# 002_PowerSupply.net
KiCad netlist of a schematic drawn in Altium Designer
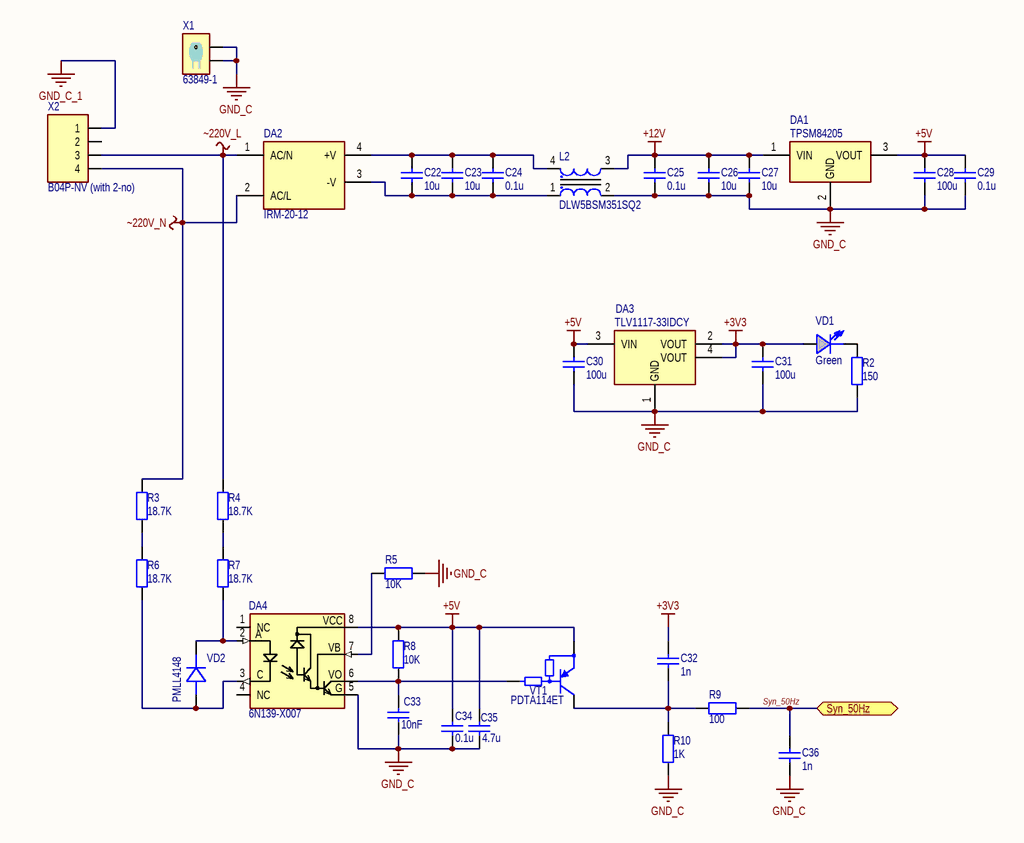
[diagram p0: 002_PowerSupply.SchDoc]

(export (version "E")
  (design (tool "Eeschema 10.0.6"))
  (components
    (comp (ref "C22")
      (value "10u")
      (footprint "mainLib:SMD_C_1206")
      (description "SMD C 1206 MURATA 25V 20% X5R")
      (fields (field (name "PARTNUMBER") "GRM31MR61E106M") (field (name "MANUFACTURER") "MURATA"))
      (libsource (lib "mainRCLib") (part "C1206 10u 25V 20%"))
    )
    (comp (ref "C23")
      (value "10u")
      (footprint "mainLib:SMD_C_1206")
      (description "SMD C 1206 MURATA 25V 20% X5R")
      (fields (field (name "PARTNUMBER") "GRM31MR61E106M") (field (name "MANUFACTURER") "MURATA"))
      (libsource (lib "mainRCLib") (part "C1206 10u 25V 20%"))
    )
    (comp (ref "C24")
      (value "0.1u")
      (footprint "mainLib:SMD_C_0603")
      (description "SMD C 0603 MURATA 50V 10% X7R")
      (fields (field (name "PARTNUMBER") "GRM188R71H104K") (field (name "MANUFACTURER") "MURATA"))
      (libsource (lib "mainRCLib") (part "C0603 0.1u 50V 10%"))
    )
    (comp (ref "C25")
      (value "0.1u")
      (footprint "mainLib:SMD_C_0603")
      (description "SMD C 0603 MURATA 50V 10% X7R")
      (fields (field (name "PARTNUMBER") "GRM188R71H104K") (field (name "MANUFACTURER") "MURATA"))
      (libsource (lib "mainRCLib") (part "C0603 0.1u 50V 10%"))
    )
    (comp (ref "C26")
      (value "10u")
      (footprint "mainLib:SMD_C_1206")
      (description "SMD C 1206 MURATA 25V 20% X5R")
      (fields (field (name "PARTNUMBER") "GRM31MR61E106M") (field (name "MANUFACTURER") "MURATA"))
      (libsource (lib "mainRCLib") (part "C1206 10u 25V 20%"))
    )
    (comp (ref "C27")
      (value "10u")
      (footprint "mainLib:SMD_C_1206")
      (description "SMD C 1206 MURATA 25V 20% X5R")
      (fields (field (name "PARTNUMBER") "GRM31MR61E106M") (field (name "MANUFACTURER") "MURATA"))
      (libsource (lib "mainRCLib") (part "C1206 10u 25V 20%"))
    )
    (comp (ref "C28")
      (value "100u")
      (footprint "mainLib:SMD_C_0805")
      (description "SMD 0805 MURATA 6.3V 20% X5R")
      (fields (field (name "PARTNUMBER") "GRM21BR60J107M") (field (name "MANUFACTURER") "MURATA"))
      (libsource (lib "mainRCLib") (part "C0805 100u 6.3V 20% X5R"))
    )
    (comp (ref "C29")
      (value "0.1u")
      (footprint "mainLib:SMD_C_0603")
      (description "SMD C 0603 MURATA 50V 10% X7R")
      (fields (field (name "PARTNUMBER") "GRM188R71H104K") (field (name "MANUFACTURER") "MURATA"))
      (libsource (lib "mainRCLib") (part "C0603 0.1u 50V 10%"))
    )
    (comp (ref "C30")
      (value "100u")
      (footprint "mainLib:SMD_C_0805")
      (description "SMD 0805 MURATA 6.3V 20% X5R")
      (fields (field (name "PARTNUMBER") "GRM21BR60J107M") (field (name "MANUFACTURER") "MURATA"))
      (libsource (lib "mainRCLib") (part "C0805 100u 6.3V 20% X5R"))
    )
    (comp (ref "C31")
      (value "100u")
      (footprint "mainLib:SMD_C_0805")
      (description "SMD 0805 MURATA 6.3V 20% X5R")
      (fields (field (name "PARTNUMBER") "GRM21BR60J107M") (field (name "MANUFACTURER") "MURATA"))
      (libsource (lib "mainRCLib") (part "C0805 100u 6.3V 20% X5R"))
    )
    (comp (ref "C32")
      (value "1n")
      (footprint "mainLib:SMD_C_0603")
      (description "SMD C 0603 MURATA 50V 5% NP0")
      (fields (field (name "PARTNUMBER") "GRM1885C1H102JA01") (field (name "MANUFACTURER") "MURATA"))
      (libsource (lib "mainRCLib") (part "C0603 1n 50V 5%"))
    )
    (comp (ref "C33")
      (value "10nF")
      (footprint "mainLib:SMD_C_0603")
      (description "SMD C 0603 MURATA 100V 10% X7R")
      (fields (field (name "PARTNUMBER") "GRJ188R72A103KE11#") (field (name "MANUFACTURER") "MURATA"))
      (libsource (lib "mainRCLib") (part "C0603 10nF 100V 10%"))
    )
    (comp (ref "C34")
      (value "0.1u")
      (footprint "mainLib:SMD_C_0603")
      (description "SMD C 0603 MURATA 50V 10% X7R")
      (fields (field (name "PARTNUMBER") "GRM188R71H104K") (field (name "MANUFACTURER") "MURATA"))
      (libsource (lib "mainRCLib") (part "C0603 0.1u 50V 10%"))
    )
    (comp (ref "C35")
      (value "4.7u")
      (footprint "mainLib:SMD_C_0805")
      (description "SMD C 0805 MURATA 50V 5% NP0")
      (fields (field (name "PARTNUMBER") "GRM21BR61E475M") (field (name "MANUFACTURER") "MURATA"))
      (libsource (lib "mainRCLib") (part "C0805 4.7u 25V 20%  X5R"))
    )
    (comp (ref "C36")
      (value "1n")
      (footprint "mainLib:SMD_C_0603")
      (description "SMD C 0603 MURATA 50V 5% NP0")
      (fields (field (name "PARTNUMBER") "GRM1885C1H102JA01") (field (name "MANUFACTURER") "MURATA"))
      (libsource (lib "mainRCLib") (part "C0603 1n 50V 5%"))
    )
    (comp (ref "DA1")
      (value "TPSM84205")
      (footprint "mainLib:EAB (SIP DCDC Module)")
      (description "1.5A 5Vout up to 28 Vin StepDown module")
      (fields (field (name "MANUFACTURER") "Texas Instrument"))
      (libsource (lib "mainLib") (part "TPSM84205"))
    )
    (comp (ref "DA2")
      (value "IRM-20-12")
      (footprint "mainLib:IRM-20-12")
      (description "20W 12VDC 1.85A PCB")
      (fields (field (name "MANUFACTURER") "Mean Well"))
      (libsource (lib "mainLib") (part "IRM-20-12"))
    )
    (comp (ref "DA3")
      (value "TLV1117-33IDCY")
      (footprint "mainLib:SOT-223_M")
      (description "Voltage regulator 3.3V 800mA")
      (fields (field (name "MANUFACTURER") "Texas Instrument"))
      (libsource (lib "mainLib") (part "TLV1117-33IDCY"))
    )
    (comp (ref "DA4")
      (value "6N139-X007")
      (footprint "mainLib:6N139-X007")
      (description "Optocoupler darlingron 5.3kV 100 kbit/s")
      (fields (field (name "MANUFACTURER") "Vishay"))
      (libsource (lib "mainLib") (part "6N139-X007"))
    )
    (comp (ref "L2")
      (value "DLW5BSM351SQ2")
      (footprint "mainLib:DLW5BS(AH)")
      (description "SMD Common Mode Choke Coil 2A Z = 350 Ohm / 100 MHz")
      (fields (field (name "MANUFACTURER") "MURATA"))
      (libsource (lib "mainLib") (part "DLW5BSM351SQ2"))
    )
    (comp (ref "R2")
      (value "150")
      (footprint "mainLib:SMD_R_0805")
      (description "SMD 0805 VISHAY 0.125W 150V 1% 100ppm")
      (fields (field (name "PARTNUMBER") "CRCW0805150RFK") (field (name "MANUFACTURER") "VISHAY"))
      (libsource (lib "mainRCLib") (part "R0805 150 1%"))
    )
    (comp (ref "R3")
      (value "18.7K")
      (footprint "mainLib:SMD_R_1206")
      (description "SMD R 1206 VISHAY 0.25W 200V 1% 100ppm")
      (fields (field (name "PARTNUMBER") "CRCW120618K7FK") (field (name "MANUFACTURER") "VISHAY"))
      (libsource (lib "mainRCLib") (part "R1206 18.7K 1%"))
    )
    (comp (ref "R4")
      (value "18.7K")
      (footprint "mainLib:SMD_R_1206")
      (description "SMD R 1206 VISHAY 0.25W 200V 1% 100ppm")
      (fields (field (name "PARTNUMBER") "CRCW120618K7FK") (field (name "MANUFACTURER") "VISHAY"))
      (libsource (lib "mainRCLib") (part "R1206 18.7K 1%"))
    )
    (comp (ref "R5")
      (value "10K")
      (footprint "SMD_R_0603")
      (description "SMD R 0603 VISHAY 0.1W 75V 1% 100ppm")
      (fields (field (name "PARTNUMBER") "CRCW060310K0FK") (field (name "MANUFACTURER") "VISHAY"))
      (libsource (lib "mainRCLib") (part "R0603 10К 1%"))
    )
    (comp (ref "R6")
      (value "18.7K")
      (footprint "mainLib:SMD_R_1206")
      (description "SMD R 1206 VISHAY 0.25W 200V 1% 100ppm")
      (fields (field (name "PARTNUMBER") "CRCW120618K7FK") (field (name "MANUFACTURER") "VISHAY"))
      (libsource (lib "mainRCLib") (part "R1206 18.7K 1%"))
    )
    (comp (ref "R7")
      (value "18.7K")
      (footprint "mainLib:SMD_R_1206")
      (description "SMD R 1206 VISHAY 0.25W 200V 1% 100ppm")
      (fields (field (name "PARTNUMBER") "CRCW120618K7FK") (field (name "MANUFACTURER") "VISHAY"))
      (libsource (lib "mainRCLib") (part "R1206 18.7K 1%"))
    )
    (comp (ref "R8")
      (value "10K")
      (footprint "mainLib:SMD_R_0805")
      (description "SMD R 0805 VISHAY 0.125W 150V 1% 100ppm")
      (fields (field (name "PARTNUMBER") "CRCW080510K0FK") (field (name "MANUFACTURER") "VISHAY"))
      (libsource (lib "mainRCLib") (part "R0805 10K 1%"))
    )
    (comp (ref "R9")
      (value "100")
      (footprint "SMD_R_0603")
      (description "SMD R 0603 VISHAY 0.1W 75V 1% 100ppm")
      (fields (field (name "PARTNUMBER") "CRCW0603100RFK") (field (name "MANUFACTURER") "VISHAY"))
      (libsource (lib "mainRCLib") (part "R0603 100 1%"))
    )
    (comp (ref "R10")
      (value "1K")
      (footprint "mainLib:SMD_R_0603")
      (description "SMD R 0603 VISHAY 0.1W 75V 1% 100ppm")
      (fields (field (name "PARTNUMBER") "CRCW06031K00FK") (field (name "MANUFACTURER") "VISHAY"))
      (libsource (lib "mainRCLib") (part "R0603 1K 1%"))
    )
    (comp (ref "VD1")
      (value "Green")
      (footprint "mainLib:SMD_LED_LL_Green")
      (description "LED Green SMD")
      (fields (field (name "PARTNUMBER") "LL-S172GC-2A") (field (name "MANUFACTURER") "Lucky Light"))
      (libsource (lib "mainLib") (part "LL-S172GC-2A"))
    )
    (comp (ref "VD2")
      (value "PMLL4148")
      (footprint "mainLib:SOD80C")
      (description "If=0.2A, Vf=1V Vrrm=100V Diode (SOD80C)")
      (fields (field (name "MANUFACTURER") "NXP Semiconductors"))
      (libsource (lib "mainLib") (part "PMLL4148"))
    )
    (comp (ref "VT1")
      (value "PDTA114ET")
      (footprint "mainLib:SOT23-3")
      (description "Digital Transistor (BRT), R1=10 kOhm, R2=10 kOhm, PNP Transistor")
      (fields (field (name "MANUFACTURER") "NXP"))
      (libsource (lib "mainLib") (part "PDTA114ET"))
    )
    (comp (ref "X1")
      (value "63849-1")
      (footprint "mainLib:63849-1")
      (description "PCB, 6.3х0.8, hole")
      (fields (field (name "MANUFACTURER") "TE Connectivity"))
      (libsource (lib "mainLib") (part "63849-1"))
    )
    (comp (ref "X2")
      (value "B04P-NV (with 2-no)")
      (footprint "mainLib:B04P-NV (with 2-no)")
      (description "NV 4 конт LS=5.0 10A 250V PCB")
      (fields (field (name "PARTNUMBER") "B04P-NV") (field (name "MANUFACTURER") "JST"))
      (libsource (lib "mainLib") (part "B04P-NV (with 2-no)"))
    )
  )
  (nets
    (net (code "1") (name "+3V3") (class "Default")
      (node (ref "C31") (pin "1") (pinfunction "1_1") (pintype "passive"))
      (node (ref "C32") (pin "2") (pinfunction "2_2") (pintype "passive"))
      (node (ref "DA3") (pin "2") (pinfunction "VOUT_2") (pintype "power_in"))
      (node (ref "DA3") (pin "4") (pinfunction "VOUT_4") (pintype "power_in"))
      (node (ref "VD1") (pin "1") (pinfunction "ANODE_1") (pintype "passive"))
    )
    (net (code "2") (name "+5V") (class "Default")
      (node (ref "C28") (pin "1") (pinfunction "1_1") (pintype "passive"))
      (node (ref "C29") (pin "2") (pinfunction "2_2") (pintype "passive"))
      (node (ref "C30") (pin "1") (pinfunction "1_1") (pintype "passive"))
      (node (ref "C34") (pin "2") (pinfunction "2_2") (pintype "passive"))
      (node (ref "C35") (pin "2") (pinfunction "2_2") (pintype "passive"))
      (node (ref "DA1") (pin "3") (pinfunction "VOUT_3") (pintype "power_in"))
      (node (ref "DA3") (pin "3") (pinfunction "VIN_3") (pintype "power_in"))
      (node (ref "DA4") (pin "8") (pinfunction "VCC_8") (pintype "power_in"))
      (node (ref "R8") (pin "2") (pinfunction "2_2") (pintype "passive"))
      (node (ref "VT1") (pin "2") (pinfunction "E_2") (pintype "passive"))
    )
    (net (code "3") (name "+12V") (class "Default")
      (node (ref "C25") (pin "2") (pinfunction "2_2") (pintype "passive"))
      (node (ref "C26") (pin "2") (pinfunction "2_2") (pintype "passive"))
      (node (ref "C27") (pin "2") (pinfunction "2_2") (pintype "passive"))
      (node (ref "DA1") (pin "1") (pinfunction "VIN_1") (pintype "power_in"))
      (node (ref "L2") (pin "3") (pinfunction "3_3") (pintype "passive"))
    )
    (net (code "4") (name "/Syn_50Hz") (class "Default")
      (node (ref "C36") (pin "2") (pinfunction "2_2") (pintype "passive"))
      (node (ref "R9") (pin "2") (pinfunction "2_2") (pintype "passive"))
    )
    (net (code "5") (name "GND_C") (class "Default")
      (node (ref "C25") (pin "1") (pinfunction "1_1") (pintype "passive"))
      (node (ref "C26") (pin "1") (pinfunction "1_1") (pintype "passive"))
      (node (ref "C27") (pin "1") (pinfunction "1_1") (pintype "passive"))
      (node (ref "C28") (pin "2") (pinfunction "2_2") (pintype "passive"))
      (node (ref "C29") (pin "1") (pinfunction "1_1") (pintype "passive"))
      (node (ref "C30") (pin "2") (pinfunction "2_2") (pintype "passive"))
      (node (ref "C31") (pin "2") (pinfunction "2_2") (pintype "passive"))
      (node (ref "C33") (pin "1") (pinfunction "1_1") (pintype "passive"))
      (node (ref "C34") (pin "1") (pinfunction "1_1") (pintype "passive"))
      (node (ref "C35") (pin "1") (pinfunction "1_1") (pintype "passive"))
      (node (ref "C36") (pin "1") (pinfunction "1_1") (pintype "passive"))
      (node (ref "DA1") (pin "2") (pinfunction "GND_2") (pintype "power_in"))
      (node (ref "DA3") (pin "1") (pinfunction "GND_1") (pintype "power_in"))
      (node (ref "DA4") (pin "5") (pinfunction "5_5") (pintype "power_in"))
      (node (ref "L2") (pin "2") (pinfunction "2_2") (pintype "passive"))
      (node (ref "R10") (pin "1") (pinfunction "1_1") (pintype "passive"))
      (node (ref "R2") (pin "1") (pinfunction "1_1") (pintype "passive"))
      (node (ref "R5") (pin "2") (pinfunction "2_2") (pintype "passive"))
      (node (ref "X1") (pin "1") (pinfunction "1_1") (pintype "passive"))
      (node (ref "X1") (pin "2") (pinfunction "2_2") (pintype "passive"))
    )
    (net (code "6") (name "GND_C_1") (class "Default")
      (node (ref "X2") (pin "1") (pinfunction "1_1") (pintype "passive"))
    )
    (net (code "7") (name "Net-(DA2-+V)") (class "Default")
      (node (ref "C22") (pin "2") (pinfunction "2_2") (pintype "passive"))
      (node (ref "C23") (pin "2") (pinfunction "2_2") (pintype "passive"))
      (node (ref "C24") (pin "2") (pinfunction "2_2") (pintype "passive"))
      (node (ref "DA2") (pin "4") (pinfunction "+V_4") (pintype "passive"))
      (node (ref "L2") (pin "4") (pinfunction "4_4") (pintype "passive"))
    )
    (net (code "8") (name "Net-(DA2--V)") (class "Default")
      (node (ref "C22") (pin "1") (pinfunction "1_1") (pintype "passive"))
      (node (ref "C23") (pin "1") (pinfunction "1_1") (pintype "passive"))
      (node (ref "C24") (pin "1") (pinfunction "1_1") (pintype "passive"))
      (node (ref "DA2") (pin "3") (pinfunction "-V_3") (pintype "passive"))
      (node (ref "L2") (pin "1") (pinfunction "1_1") (pintype "passive"))
    )
    (net (code "9") (name "Net-(DA4-C)") (class "Default")
      (node (ref "DA4") (pin "3") (pinfunction "C_3") (pintype "output"))
      (node (ref "R6") (pin "1") (pinfunction "1_1") (pintype "passive"))
      (node (ref "VD2") (pin "1") (pinfunction "ANODE_1") (pintype "passive"))
    )
    (net (code "10") (name "Net-(DA4-VB)") (class "Default")
      (node (ref "DA4") (pin "7") (pinfunction "VB_7") (pintype "input"))
      (node (ref "R5") (pin "1") (pinfunction "1_1") (pintype "passive"))
    )
    (net (code "11") (name "Net-(R3-Pad1)") (class "Default")
      (node (ref "R3") (pin "1") (pinfunction "1_1") (pintype "passive"))
      (node (ref "R6") (pin "2") (pinfunction "2_2") (pintype "passive"))
    )
    (net (code "12") (name "Net-(R4-Pad1)") (class "Default")
      (node (ref "R4") (pin "1") (pinfunction "1_1") (pintype "passive"))
      (node (ref "R7") (pin "2") (pinfunction "2_2") (pintype "passive"))
    )
    (net (code "13") (name "Net-(VD1-CATHODE)") (class "Default")
      (node (ref "R2") (pin "2") (pinfunction "2_2") (pintype "passive"))
      (node (ref "VD1") (pin "2") (pinfunction "CATHODE_2") (pintype "passive"))
    )
    (net (code "14") (name "Net-(VD2-CATHODE)") (class "Default")
      (node (ref "DA4") (pin "2") (pinfunction "2_2") (pintype "input"))
      (node (ref "R7") (pin "1") (pinfunction "1_1") (pintype "passive"))
      (node (ref "VD2") (pin "2") (pinfunction "CATHODE_2") (pintype "passive"))
    )
    (net (code "15") (name "Net-(VT1-B)") (class "Default")
      (node (ref "C33") (pin "2") (pinfunction "2_2") (pintype "passive"))
      (node (ref "DA4") (pin "6") (pinfunction "6_6") (pintype "open_collector"))
      (node (ref "R8") (pin "1") (pinfunction "1_1") (pintype "passive"))
      (node (ref "VT1") (pin "1") (pinfunction "B_1") (pintype "passive"))
    )
    (net (code "16") (name "Net-(VT1-C)") (class "Default")
      (node (ref "C32") (pin "1") (pinfunction "1_1") (pintype "passive"))
      (node (ref "R10") (pin "2") (pinfunction "2_2") (pintype "passive"))
      (node (ref "R9") (pin "1") (pinfunction "1_1") (pintype "passive"))
      (node (ref "VT1") (pin "3") (pinfunction "C_3") (pintype "passive"))
    )
    (net (code "17") (name "unconnected-(DA4-NC-Pad1)") (class "Default")
      (node (ref "DA4") (pin "1") (pinfunction "NC_1") (pintype "passive"))
    )
    (net (code "18") (name "unconnected-(DA4-NC-Pad4)") (class "Default")
      (node (ref "DA4") (pin "4") (pinfunction "NC_4") (pintype "passive"))
    )
    (net (code "19") (name "unconnected-(X2-Pad2)") (class "Default")
      (node (ref "X2") (pin "2") (pinfunction "2_2") (pintype "passive"))
    )
    (net (code "20") (name "~220V_L") (class "Default")
      (node (ref "DA2") (pin "1") (pinfunction "AC/N_1") (pintype "passive"))
      (node (ref "R4") (pin "2") (pinfunction "2_2") (pintype "passive"))
      (node (ref "X2") (pin "3") (pinfunction "3_3") (pintype "passive"))
    )
    (net (code "21") (name "~220V_N") (class "Default")
      (node (ref "DA2") (pin "2") (pinfunction "AC/L_2") (pintype "passive"))
      (node (ref "R3") (pin "2") (pinfunction "2_2") (pintype "passive"))
      (node (ref "X2") (pin "4") (pinfunction "4_4") (pintype "passive"))
    )
  )
)
